# SCH_More-PCB_2025-03-30.net
KiCad netlist of a schematic drawn in EasyEDA
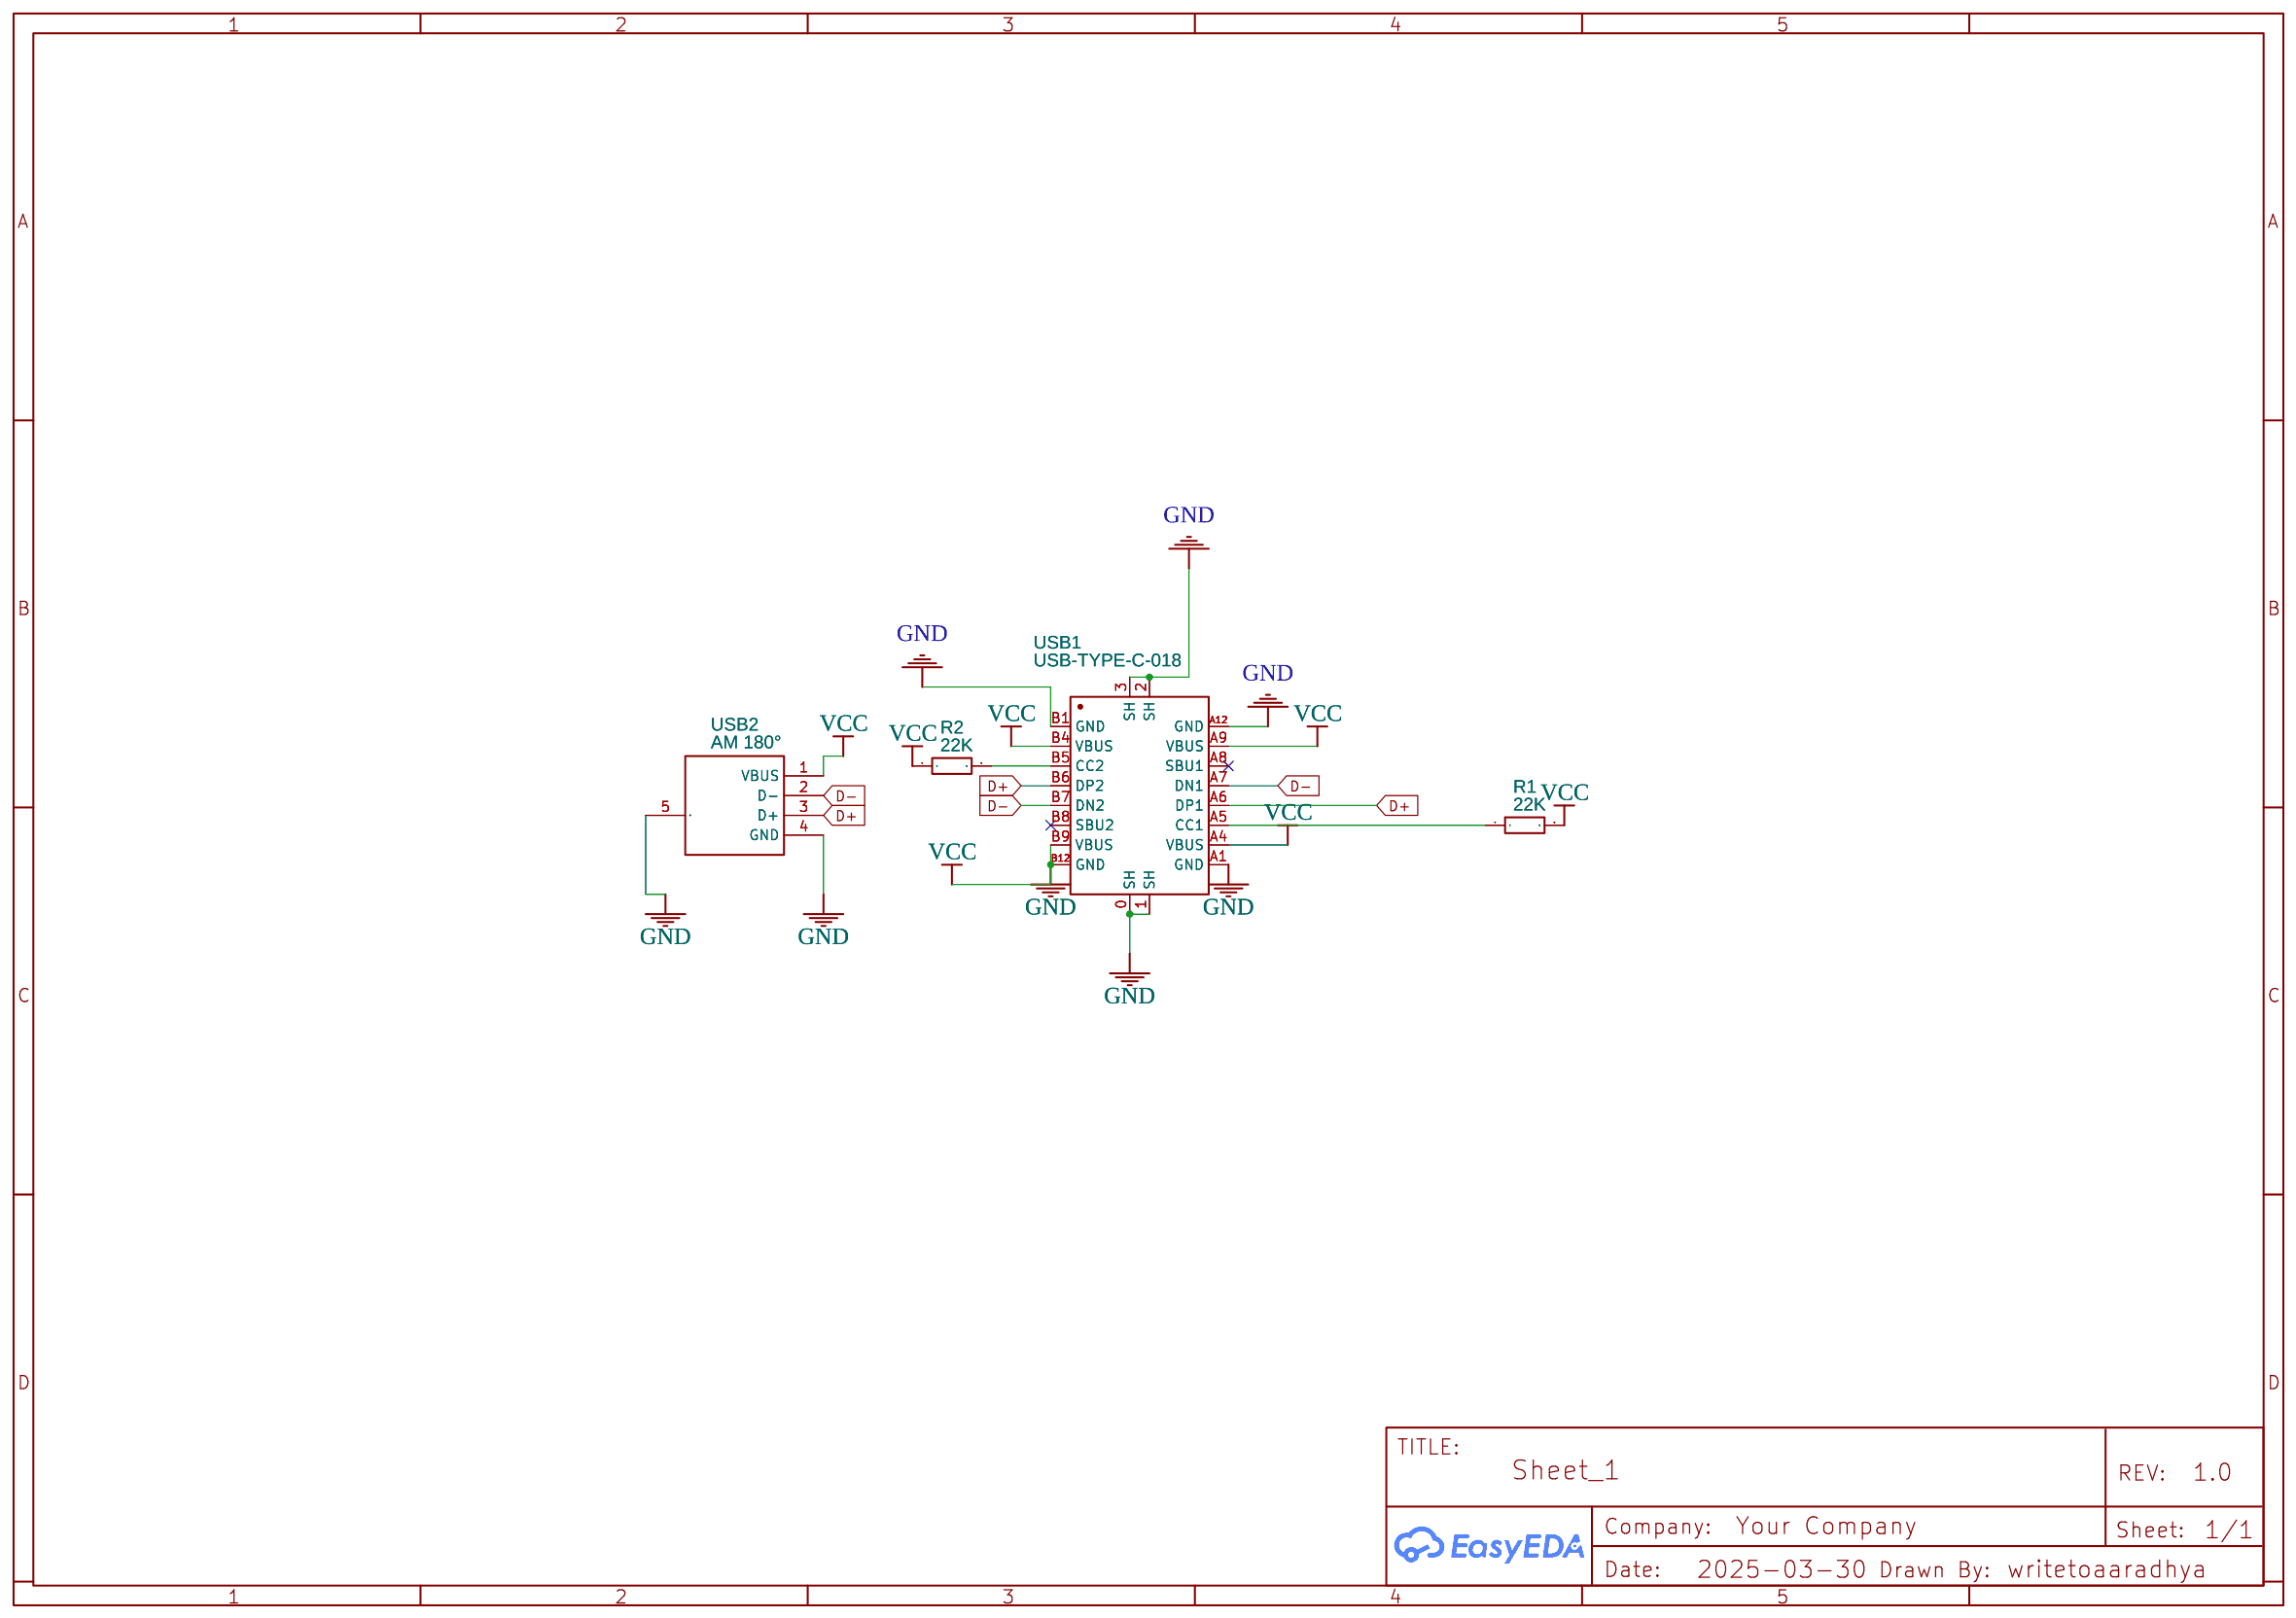
[diagram p0: schematic sheet]

(export (version "E")
  (design (tool "Eeschema 10.0.6"))
  (components
    (comp (ref "R1")
      (value "22K")
      (fields (field (name "Manufacturer Part") "ERTJ0ER223J") (field (name "Manufacturer") "PANASONIC(松下)"))
      (libsource (lib "") (part "ERTJ0ER223J"))
    )
    (comp (ref "R2")
      (value "22K")
      (fields (field (name "Manufacturer Part") "ERTJ0ER223J") (field (name "Manufacturer") "PANASONIC(松下)"))
      (libsource (lib "") (part "ERTJ0ER223J"))
    )
    (comp (ref "USB1")
      (value "USB-TYPE-C-018")
      (fields (field (name "Manufacturer") "DEALON(德艺隆)"))
      (libsource (lib "") (part "USB-TYPE-C-018"))
    )
    (comp (ref "USB2")
      (value "AM 180°")
      (fields (field (name "Manufacturer") "SHOU HAN(首韩)"))
      (libsource (lib "") (part "AM 180°"))
    )
  )
  (nets
    (net (code "1") (name "D+") (class "Default")
      (node (ref "USB1") (pin "A6") (pinfunction "DP1_A6") (pintype "unspecified"))
      (node (ref "USB1") (pin "B6") (pinfunction "DP2_B6") (pintype "unspecified"))
      (node (ref "USB2") (pin "3") (pinfunction "D+_3") (pintype "input"))
    )
    (net (code "2") (name "D-") (class "Default")
      (node (ref "USB1") (pin "A7") (pinfunction "DN1_A7") (pintype "unspecified"))
      (node (ref "USB1") (pin "B7") (pinfunction "DN2_B7") (pintype "unspecified"))
      (node (ref "USB2") (pin "2") (pinfunction "D-_2") (pintype "input"))
    )
    (net (code "3") (name "GND") (class "Default")
      (node (ref "R1") (pin "2") (pinfunction "2_2") (pintype "unspecified"))
      (node (ref "R2") (pin "1") (pinfunction "1_1") (pintype "unspecified"))
      (node (ref "USB1") (pin "0") (pinfunction "SH_0") (pintype "unspecified"))
      (node (ref "USB1") (pin "1") (pinfunction "SH_1") (pintype "unspecified"))
      (node (ref "USB1") (pin "2") (pinfunction "SH_2") (pintype "unspecified"))
      (node (ref "USB1") (pin "3") (pinfunction "SH_3") (pintype "unspecified"))
      (node (ref "USB1") (pin "A1") (pinfunction "GND_A1") (pintype "unspecified"))
      (node (ref "USB1") (pin "A12") (pinfunction "GND_A12") (pintype "unspecified"))
      (node (ref "USB1") (pin "A4") (pinfunction "VBUS_A4") (pintype "unspecified"))
      (node (ref "USB1") (pin "A9") (pinfunction "VBUS_A9") (pintype "unspecified"))
      (node (ref "USB1") (pin "B1") (pinfunction "GND_B1") (pintype "unspecified"))
      (node (ref "USB1") (pin "B12") (pinfunction "GND_B12") (pintype "unspecified"))
      (node (ref "USB1") (pin "B4") (pinfunction "VBUS_B4") (pintype "unspecified"))
      (node (ref "USB1") (pin "B9") (pinfunction "VBUS_B9") (pintype "unspecified"))
      (node (ref "USB2") (pin "1") (pinfunction "VBUS_1") (pintype "input"))
      (node (ref "USB2") (pin "4") (pinfunction "GND_4") (pintype "input"))
      (node (ref "USB2") (pin "5") (pinfunction "EH_5") (pintype "input"))
    )
    (net (code "4") (name "Net-(USB1-CC1)") (class "Default")
      (node (ref "R1") (pin "1") (pinfunction "1_1") (pintype "unspecified"))
      (node (ref "USB1") (pin "A5") (pinfunction "CC1_A5") (pintype "unspecified"))
    )
    (net (code "5") (name "Net-(USB1-CC2)") (class "Default")
      (node (ref "R2") (pin "2") (pinfunction "2_2") (pintype "unspecified"))
      (node (ref "USB1") (pin "B5") (pinfunction "CC2_B5") (pintype "unspecified"))
    )
    (net (code "6") (name "unconnected-(USB1-SBU1-PadA8)") (class "Default")
      (node (ref "USB1") (pin "A8") (pinfunction "SBU1_A8") (pintype "unspecified+no_connect"))
    )
    (net (code "7") (name "unconnected-(USB1-SBU2-PadB8)") (class "Default")
      (node (ref "USB1") (pin "B8") (pinfunction "SBU2_B8") (pintype "unspecified+no_connect"))
    )
  )
)
